# electric-imp-shield-v11.net
KiCad netlist of a schematic drawn in EAGLE
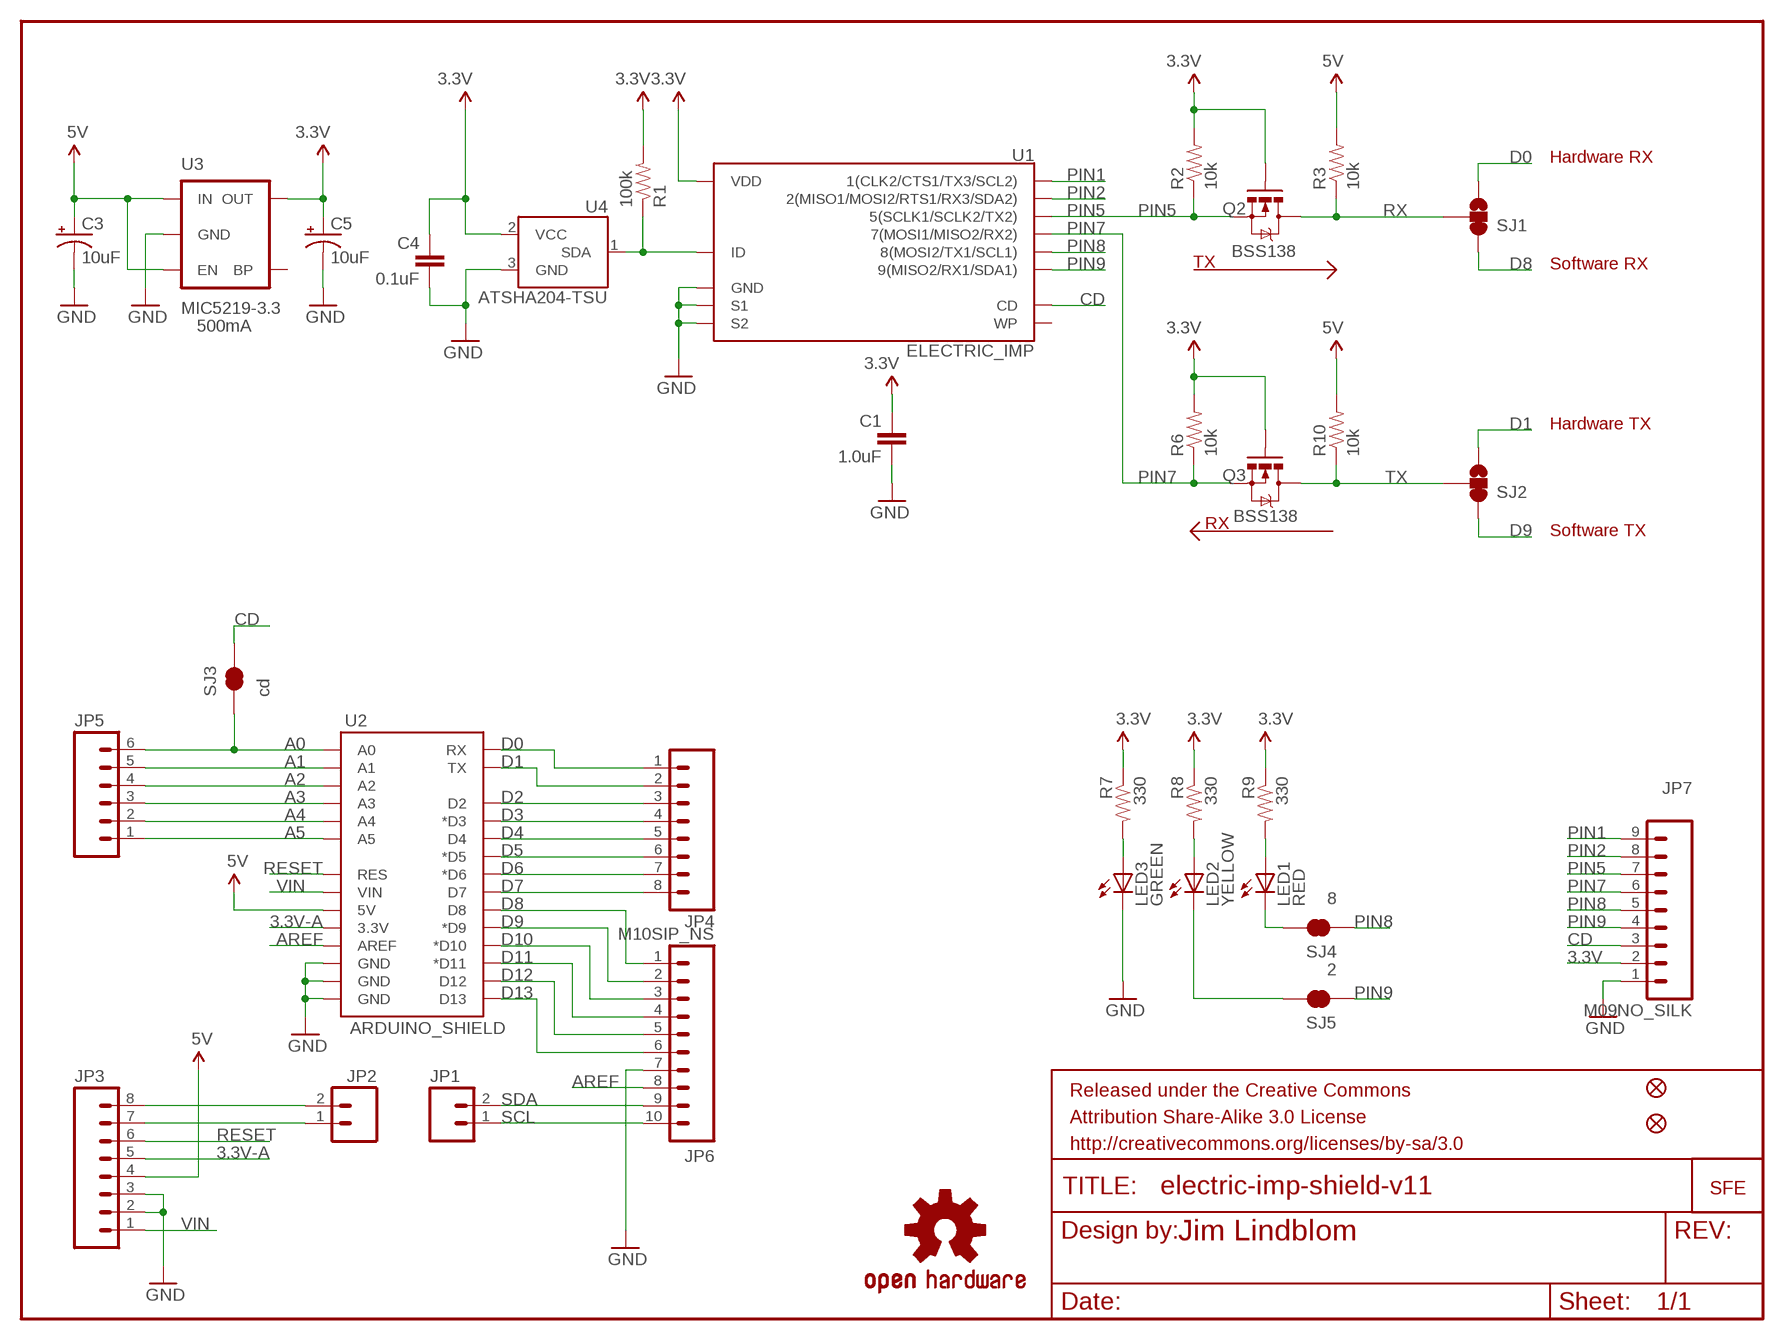
[diagram p0: schematic, sheet 1]

(export (version "E")
  (design (tool "Eeschema 10.0.6"))
  (components
    (comp (ref "C1")
      (value "1.0uF")
      (footprint "eagle-import:0402-CAP")
      (libsource (lib "eagle-import") (part "CAP0402-CAP"))
    )
    (comp (ref "C3")
      (value "10uF")
      (footprint "eagle-import:EIA3216")
      (libsource (lib "eagle-import") (part "CAP_POL1206"))
    )
    (comp (ref "C4")
      (value "0.1uF")
      (footprint "eagle-import:0402-CAP")
      (libsource (lib "eagle-import") (part "CAP0402-CAP"))
    )
    (comp (ref "C5")
      (value "10uF")
      (footprint "eagle-import:EIA3216")
      (libsource (lib "eagle-import") (part "CAP_POL1206"))
    )
    (comp (ref "JP1")
      (value "M021X02_NO_SILK")
      (footprint "eagle-import:1X02_NO_SILK")
      (libsource (lib "eagle-import") (part "M021X02_NO_SILK"))
    )
    (comp (ref "JP2")
      (value "M021X02_NO_SILK")
      (footprint "eagle-import:1X02_NO_SILK")
      (libsource (lib "eagle-import") (part "M021X02_NO_SILK"))
    )
    (comp (ref "JP3")
      (value "M08SIP_NS")
      (footprint "eagle-import:1X08_NO_SILK")
      (libsource (lib "eagle-import") (part "M08SIP_NS"))
    )
    (comp (ref "JP4")
      (value "M08SIP_NS")
      (footprint "eagle-import:1X08_NO_SILK")
      (libsource (lib "eagle-import") (part "M08SIP_NS"))
    )
    (comp (ref "JP5")
      (value "M06SIP_NS")
      (footprint "eagle-import:1X06_NO_SILK")
      (libsource (lib "eagle-import") (part "M06SIP_NS"))
    )
    (comp (ref "JP6")
      (value "M10SIP_NS")
      (footprint "eagle-import:1X10_NO_SILK")
      (libsource (lib "eagle-import") (part "M10SIP_NS"))
    )
    (comp (ref "JP7")
      (value "M09NO_SILK")
      (footprint "eagle-import:1X09_NO_SILK")
      (libsource (lib "eagle-import") (part "M09NO_SILK"))
    )
    (comp (ref "JP8")
      (value "FIDUCIALUFIDUCIAL")
      (footprint "eagle-import:MICRO-FIDUCIAL")
      (libsource (lib "eagle-import") (part "FIDUCIALUFIDUCIAL"))
    )
    (comp (ref "JP9")
      (value "FIDUCIALUFIDUCIAL")
      (footprint "eagle-import:MICRO-FIDUCIAL")
      (libsource (lib "eagle-import") (part "FIDUCIALUFIDUCIAL"))
    )
    (comp (ref "JP10")
      (value "LOGO-SFENW2")
      (footprint "eagle-import:SFE-NEW-WEB")
      (libsource (lib "eagle-import") (part "LOGO-SFENW2"))
    )
    (comp (ref "LED1")
      (value "RED")
      (footprint "eagle-import:LED-0603")
      (libsource (lib "eagle-import") (part "LED0603"))
    )
    (comp (ref "LED2")
      (value "YELLOW")
      (footprint "eagle-import:LED-0603")
      (libsource (lib "eagle-import") (part "LED0603"))
    )
    (comp (ref "LED3")
      (value "GREEN")
      (footprint "eagle-import:LED-0603")
      (libsource (lib "eagle-import") (part "LED0603"))
    )
    (comp (ref "Q2")
      (value "BSS138")
      (footprint "eagle-import:SOT23-3")
      (libsource (lib "eagle-import") (part "MOSFET-NCHANNELSMD"))
    )
    (comp (ref "Q3")
      (value "BSS138")
      (footprint "eagle-import:SOT23-3")
      (libsource (lib "eagle-import") (part "MOSFET-NCHANNELSMD"))
    )
    (comp (ref "R1")
      (value "100k")
      (footprint "eagle-import:0402-RES")
      (libsource (lib "eagle-import") (part "RESISTOR0402-RES"))
    )
    (comp (ref "R2")
      (value "10k")
      (footprint "eagle-import:0402-RES")
      (libsource (lib "eagle-import") (part "RESISTOR0402-RES"))
    )
    (comp (ref "R3")
      (value "10k")
      (footprint "eagle-import:0402-RES")
      (libsource (lib "eagle-import") (part "RESISTOR0402-RES"))
    )
    (comp (ref "R6")
      (value "10k")
      (footprint "eagle-import:0402-RES")
      (libsource (lib "eagle-import") (part "RESISTOR0402-RES"))
    )
    (comp (ref "R7")
      (value "330")
      (footprint "eagle-import:0402-RES")
      (libsource (lib "eagle-import") (part "RESISTOR0402-RES"))
    )
    (comp (ref "R8")
      (value "330")
      (footprint "eagle-import:0402-RES")
      (libsource (lib "eagle-import") (part "RESISTOR0402-RES"))
    )
    (comp (ref "R9")
      (value "330")
      (footprint "eagle-import:0402-RES")
      (libsource (lib "eagle-import") (part "RESISTOR0402-RES"))
    )
    (comp (ref "R10")
      (value "10k")
      (footprint "eagle-import:0402-RES")
      (libsource (lib "eagle-import") (part "RESISTOR0402-RES"))
    )
    (comp (ref "SJ1")
      (value "SOLDERJUMPER_2WAYS")
      (footprint "eagle-import:SJ_3")
      (libsource (lib "eagle-import") (part "SOLDERJUMPER_2WAYS"))
    )
    (comp (ref "SJ2")
      (value "SOLDERJUMPER_2WAYS")
      (footprint "eagle-import:SJ_3")
      (libsource (lib "eagle-import") (part "SOLDERJUMPER_2WAYS"))
    )
    (comp (ref "SJ3")
      (value "cd")
      (footprint "eagle-import:SJ_2S-TRACE")
      (libsource (lib "eagle-import") (part "SOLDERJUMPERTRACE"))
    )
    (comp (ref "SJ4")
      (value "8")
      (footprint "eagle-import:SJ_2S-TRACE")
      (libsource (lib "eagle-import") (part "SOLDERJUMPERTRACE"))
    )
    (comp (ref "SJ5")
      (value "2")
      (footprint "eagle-import:SJ_2S-TRACE")
      (libsource (lib "eagle-import") (part "SOLDERJUMPERTRACE"))
    )
    (comp (ref "U$7")
      (value "OSHW-LOGOS")
      (footprint "eagle-import:OSHW-LOGO-S")
      (libsource (lib "eagle-import") (part "OSHW-LOGOS"))
    )
    (comp (ref "U1")
      (value "ELECTRIC_IMP")
      (footprint "eagle-import:SD_MMC_SOCKET")
      (libsource (lib "eagle-import") (part "ELECTRIC_IMP"))
    )
    (comp (ref "U2")
      (value "ARDUINO_SHIELD")
      (footprint "eagle-import:DUEMILANOVE_SHIELD_NOHOLES_NOLABELS")
      (libsource (lib "eagle-import") (part "ARDUINO_SHIELDNOHOLESORLABELS"))
    )
    (comp (ref "U3")
      (value "MIC5219-3.3")
      (footprint "eagle-import:SOT23-5")
      (libsource (lib "eagle-import") (part "V_REG_LDOSMD"))
    )
    (comp (ref "U4")
      (value "ATSHA204-TSU")
      (footprint "eagle-import:SOT23-3")
      (libsource (lib "eagle-import") (part "ATSHA204-TSU"))
    )
  )
  (nets
    (net (code "1") (name "/3.3V-A") (class "Default")
      (node (ref "JP3") (pin "5") (pinfunction "5_5") (pintype "passive"))
      (node (ref "U2") (pin "3.3V") (pinfunction "3.3V_3.3V") (pintype "bidirectional"))
    )
    (net (code "2") (name "/A0") (class "Default")
      (node (ref "JP5") (pin "6") (pinfunction "6_6") (pintype "passive"))
      (node (ref "SJ3") (pin "1") (pinfunction "1_1") (pintype "passive"))
      (node (ref "U2") (pin "A0") (pinfunction "A0_A0") (pintype "bidirectional"))
    )
    (net (code "3") (name "/A1") (class "Default")
      (node (ref "JP5") (pin "5") (pinfunction "5_5") (pintype "passive"))
      (node (ref "U2") (pin "A1") (pinfunction "A1_A1") (pintype "bidirectional"))
    )
    (net (code "4") (name "/A2") (class "Default")
      (node (ref "JP5") (pin "4") (pinfunction "4_4") (pintype "passive"))
      (node (ref "U2") (pin "A2") (pinfunction "A2_A2") (pintype "bidirectional"))
    )
    (net (code "5") (name "/A3") (class "Default")
      (node (ref "JP5") (pin "3") (pinfunction "3_3") (pintype "passive"))
      (node (ref "U2") (pin "A3") (pinfunction "A3_A3") (pintype "bidirectional"))
    )
    (net (code "6") (name "/A4") (class "Default")
      (node (ref "JP5") (pin "2") (pinfunction "2_2") (pintype "passive"))
      (node (ref "U2") (pin "A4") (pinfunction "A4_A4") (pintype "bidirectional"))
    )
    (net (code "7") (name "/A5") (class "Default")
      (node (ref "JP5") (pin "1") (pinfunction "1_1") (pintype "passive"))
      (node (ref "U2") (pin "A5") (pinfunction "A5_A5") (pintype "bidirectional"))
    )
    (net (code "8") (name "/AREF") (class "Default")
      (node (ref "JP6") (pin "8") (pinfunction "8_8") (pintype "passive"))
      (node (ref "U2") (pin "AREF") (pinfunction "AREF_AREF") (pintype "bidirectional"))
    )
    (net (code "9") (name "/CD") (class "Default")
      (node (ref "JP7") (pin "3") (pinfunction "3_3") (pintype "passive"))
      (node (ref "SJ3") (pin "2") (pinfunction "2_2") (pintype "passive"))
      (node (ref "U1") (pin "CD") (pinfunction "CD_CD") (pintype "bidirectional"))
    )
    (net (code "10") (name "/D0") (class "Default")
      (node (ref "JP4") (pin "1") (pinfunction "1_1") (pintype "passive"))
      (node (ref "SJ1") (pin "3") (pinfunction "3_3") (pintype "passive"))
      (node (ref "U2") (pin "RX") (pinfunction "RX_RX") (pintype "bidirectional"))
    )
    (net (code "11") (name "/D1") (class "Default")
      (node (ref "JP4") (pin "2") (pinfunction "2_2") (pintype "passive"))
      (node (ref "SJ2") (pin "3") (pinfunction "3_3") (pintype "passive"))
      (node (ref "U2") (pin "TX") (pinfunction "TX_TX") (pintype "bidirectional"))
    )
    (net (code "12") (name "/D2") (class "Default")
      (node (ref "JP4") (pin "3") (pinfunction "3_3") (pintype "passive"))
      (node (ref "U2") (pin "D2") (pinfunction "D2_D2") (pintype "bidirectional"))
    )
    (net (code "13") (name "/D3") (class "Default")
      (node (ref "JP4") (pin "4") (pinfunction "4_4") (pintype "passive"))
      (node (ref "U2") (pin "D3") (pinfunction "*D3_D3") (pintype "bidirectional"))
    )
    (net (code "14") (name "/D4") (class "Default")
      (node (ref "JP4") (pin "5") (pinfunction "5_5") (pintype "passive"))
      (node (ref "U2") (pin "D4") (pinfunction "D4_D4") (pintype "bidirectional"))
    )
    (net (code "15") (name "/D5") (class "Default")
      (node (ref "JP4") (pin "6") (pinfunction "6_6") (pintype "passive"))
      (node (ref "U2") (pin "D5") (pinfunction "*D5_D5") (pintype "bidirectional"))
    )
    (net (code "16") (name "/D6") (class "Default")
      (node (ref "JP4") (pin "7") (pinfunction "7_7") (pintype "passive"))
      (node (ref "U2") (pin "D6") (pinfunction "*D6_D6") (pintype "bidirectional"))
    )
    (net (code "17") (name "/D7") (class "Default")
      (node (ref "JP4") (pin "8") (pinfunction "8_8") (pintype "passive"))
      (node (ref "U2") (pin "D7") (pinfunction "D7_D7") (pintype "bidirectional"))
    )
    (net (code "18") (name "/D8") (class "Default")
      (node (ref "JP6") (pin "1") (pinfunction "1_1") (pintype "passive"))
      (node (ref "SJ1") (pin "1") (pinfunction "1_1") (pintype "passive"))
      (node (ref "U2") (pin "D8") (pinfunction "D8_D8") (pintype "bidirectional"))
    )
    (net (code "19") (name "/D9") (class "Default")
      (node (ref "JP6") (pin "2") (pinfunction "2_2") (pintype "passive"))
      (node (ref "SJ2") (pin "1") (pinfunction "1_1") (pintype "passive"))
      (node (ref "U2") (pin "D9") (pinfunction "*D9_D9") (pintype "bidirectional"))
    )
    (net (code "20") (name "/D10") (class "Default")
      (node (ref "JP6") (pin "3") (pinfunction "3_3") (pintype "passive"))
      (node (ref "U2") (pin "D10") (pinfunction "*D10_D10") (pintype "bidirectional"))
    )
    (net (code "21") (name "/D11") (class "Default")
      (node (ref "JP6") (pin "4") (pinfunction "4_4") (pintype "passive"))
      (node (ref "U2") (pin "D11") (pinfunction "*D11_D11") (pintype "bidirectional"))
    )
    (net (code "22") (name "/D12") (class "Default")
      (node (ref "JP6") (pin "5") (pinfunction "5_5") (pintype "passive"))
      (node (ref "U2") (pin "D12") (pinfunction "D12_D12") (pintype "bidirectional"))
    )
    (net (code "23") (name "/D13") (class "Default")
      (node (ref "JP6") (pin "6") (pinfunction "6_6") (pintype "passive"))
      (node (ref "U2") (pin "D13") (pinfunction "D13_D13") (pintype "bidirectional"))
    )
    (net (code "24") (name "/PIN1") (class "Default")
      (node (ref "JP7") (pin "9") (pinfunction "9_9") (pintype "passive"))
      (node (ref "U1") (pin "1") (pinfunction "1(CLK2/CTS1/TX3/SCL2)_1") (pintype "bidirectional"))
    )
    (net (code "25") (name "/PIN2") (class "Default")
      (node (ref "JP7") (pin "8") (pinfunction "8_8") (pintype "passive"))
      (node (ref "U1") (pin "2") (pinfunction "2(MISO1/MOSI2/RTS1/RX3/SDA2)_2") (pintype "bidirectional"))
    )
    (net (code "26") (name "/PIN5") (class "Default")
      (node (ref "JP7") (pin "7") (pinfunction "7_7") (pintype "passive"))
      (node (ref "Q2") (pin "2") (pinfunction "S_2") (pintype "passive"))
      (node (ref "R2") (pin "1") (pinfunction "1_1") (pintype "passive"))
      (node (ref "U1") (pin "5") (pinfunction "5(SCLK1/SCLK2/TX2)_5") (pintype "bidirectional"))
    )
    (net (code "27") (name "/PIN7") (class "Default")
      (node (ref "JP7") (pin "6") (pinfunction "6_6") (pintype "passive"))
      (node (ref "Q3") (pin "2") (pinfunction "S_2") (pintype "passive"))
      (node (ref "R6") (pin "1") (pinfunction "1_1") (pintype "passive"))
      (node (ref "U1") (pin "7") (pinfunction "7(MOSI1/MISO2/RX2)_7") (pintype "bidirectional"))
    )
    (net (code "28") (name "/PIN8") (class "Default")
      (node (ref "JP7") (pin "5") (pinfunction "5_5") (pintype "passive"))
      (node (ref "SJ4") (pin "1") (pinfunction "1_1") (pintype "passive"))
      (node (ref "U1") (pin "8") (pinfunction "8(MOSI2/TX1/SCL1)_8") (pintype "bidirectional"))
    )
    (net (code "29") (name "/PIN9") (class "Default")
      (node (ref "JP7") (pin "4") (pinfunction "4_4") (pintype "passive"))
      (node (ref "SJ5") (pin "1") (pinfunction "1_1") (pintype "passive"))
      (node (ref "U1") (pin "9") (pinfunction "9(MISO2/RX1/SDA1)_9") (pintype "bidirectional"))
    )
    (net (code "30") (name "/RESET") (class "Default")
      (node (ref "JP3") (pin "6") (pinfunction "6_6") (pintype "passive"))
      (node (ref "U2") (pin "RES") (pinfunction "RES_RES") (pintype "bidirectional"))
    )
    (net (code "31") (name "/RX") (class "Default")
      (node (ref "Q2") (pin "3") (pinfunction "D_3") (pintype "passive"))
      (node (ref "R3") (pin "1") (pinfunction "1_1") (pintype "passive"))
      (node (ref "SJ1") (pin "2") (pinfunction "2_2") (pintype "passive"))
    )
    (net (code "32") (name "/SCL") (class "Default")
      (node (ref "JP1") (pin "1") (pinfunction "1_1") (pintype "passive"))
      (node (ref "JP6") (pin "10") (pinfunction "10_10") (pintype "passive"))
    )
    (net (code "33") (name "/SDA") (class "Default")
      (node (ref "JP1") (pin "2") (pinfunction "2_2") (pintype "passive"))
      (node (ref "JP6") (pin "9") (pinfunction "9_9") (pintype "passive"))
    )
    (net (code "34") (name "/TX") (class "Default")
      (node (ref "Q3") (pin "3") (pinfunction "D_3") (pintype "passive"))
      (node (ref "R10") (pin "1") (pinfunction "1_1") (pintype "passive"))
      (node (ref "SJ2") (pin "2") (pinfunction "2_2") (pintype "passive"))
    )
    (net (code "35") (name "/VIN") (class "Default")
      (node (ref "JP3") (pin "1") (pinfunction "1_1") (pintype "passive"))
      (node (ref "U2") (pin "VIN") (pinfunction "VIN_VIN") (pintype "bidirectional"))
    )
    (net (code "36") (name "3.3V") (class "Default")
      (node (ref "C1") (pin "1") (pinfunction "1_1") (pintype "passive"))
      (node (ref "C4") (pin "1") (pinfunction "1_1") (pintype "passive"))
      (node (ref "C5") (pin "A") (pinfunction "+_A") (pintype "passive"))
      (node (ref "JP7") (pin "2") (pinfunction "2_2") (pintype "passive"))
      (node (ref "Q2") (pin "1") (pinfunction "G_1") (pintype "passive"))
      (node (ref "Q3") (pin "1") (pinfunction "G_1") (pintype "passive"))
      (node (ref "R1") (pin "2") (pinfunction "2_2") (pintype "passive"))
      (node (ref "R2") (pin "2") (pinfunction "2_2") (pintype "passive"))
      (node (ref "R6") (pin "2") (pinfunction "2_2") (pintype "passive"))
      (node (ref "R7") (pin "1") (pinfunction "1_1") (pintype "passive"))
      (node (ref "R8") (pin "1") (pinfunction "1_1") (pintype "passive"))
      (node (ref "R9") (pin "1") (pinfunction "1_1") (pintype "passive"))
      (node (ref "U1") (pin "4") (pinfunction "VDD_4") (pintype "bidirectional"))
      (node (ref "U3") (pin "5") (pinfunction "OUT_5") (pintype "passive"))
      (node (ref "U4") (pin "2") (pinfunction "VCC_2") (pintype "bidirectional"))
    )
    (net (code "37") (name "5V") (class "Default")
      (node (ref "C3") (pin "A") (pinfunction "+_A") (pintype "passive"))
      (node (ref "JP3") (pin "4") (pinfunction "4_4") (pintype "passive"))
      (node (ref "R10") (pin "2") (pinfunction "2_2") (pintype "passive"))
      (node (ref "R3") (pin "2") (pinfunction "2_2") (pintype "passive"))
      (node (ref "U2") (pin "5V") (pinfunction "5V_5V") (pintype "bidirectional"))
      (node (ref "U3") (pin "1") (pinfunction "IN_1") (pintype "input"))
      (node (ref "U3") (pin "3") (pinfunction "EN_3") (pintype "input"))
    )
    (net (code "38") (name "GND") (class "Default")
      (node (ref "C1") (pin "2") (pinfunction "2_2") (pintype "passive"))
      (node (ref "C3") (pin "C") (pinfunction "-_C") (pintype "passive"))
      (node (ref "C4") (pin "2") (pinfunction "2_2") (pintype "passive"))
      (node (ref "C5") (pin "C") (pinfunction "-_C") (pintype "passive"))
      (node (ref "JP3") (pin "2") (pinfunction "2_2") (pintype "passive"))
      (node (ref "JP3") (pin "3") (pinfunction "3_3") (pintype "passive"))
      (node (ref "JP6") (pin "7") (pinfunction "7_7") (pintype "passive"))
      (node (ref "JP7") (pin "1") (pinfunction "1_1") (pintype "passive"))
      (node (ref "LED3") (pin "C") (pinfunction "C_C") (pintype "passive"))
      (node (ref "U1") (pin "3") (pinfunction "GND_3") (pintype "bidirectional"))
      (node (ref "U1") (pin "S1") (pinfunction "S1_S1") (pintype "bidirectional"))
      (node (ref "U1") (pin "S2") (pinfunction "S2_S2") (pintype "bidirectional"))
      (node (ref "U2") (pin "GND@0") (pinfunction "GND_GND@0") (pintype "bidirectional"))
      (node (ref "U2") (pin "GND@1") (pinfunction "GND_GND@1") (pintype "bidirectional"))
      (node (ref "U2") (pin "GND@2") (pinfunction "GND_GND@2") (pintype "bidirectional"))
      (node (ref "U3") (pin "2") (pinfunction "GND_2") (pintype "input"))
      (node (ref "U4") (pin "3") (pinfunction "GND_3") (pintype "bidirectional"))
    )
    (net (code "39") (name "Net-(JP2-Pad1)") (class "Default")
      (node (ref "JP2") (pin "1") (pinfunction "1_1") (pintype "passive"))
      (node (ref "JP3") (pin "7") (pinfunction "7_7") (pintype "passive"))
    )
    (net (code "40") (name "Net-(JP2-Pad2)") (class "Default")
      (node (ref "JP2") (pin "2") (pinfunction "2_2") (pintype "passive"))
      (node (ref "JP3") (pin "8") (pinfunction "8_8") (pintype "passive"))
    )
    (net (code "41") (name "Net-(LED1-PadA)") (class "Default")
      (node (ref "LED1") (pin "A") (pinfunction "A_A") (pintype "passive"))
      (node (ref "R9") (pin "2") (pinfunction "2_2") (pintype "passive"))
    )
    (net (code "42") (name "Net-(LED1-PadC)") (class "Default")
      (node (ref "LED1") (pin "C") (pinfunction "C_C") (pintype "passive"))
      (node (ref "SJ4") (pin "2") (pinfunction "2_2") (pintype "passive"))
    )
    (net (code "43") (name "Net-(LED2-PadA)") (class "Default")
      (node (ref "LED2") (pin "A") (pinfunction "A_A") (pintype "passive"))
      (node (ref "R8") (pin "2") (pinfunction "2_2") (pintype "passive"))
    )
    (net (code "44") (name "Net-(LED2-PadC)") (class "Default")
      (node (ref "LED2") (pin "C") (pinfunction "C_C") (pintype "passive"))
      (node (ref "SJ5") (pin "2") (pinfunction "2_2") (pintype "passive"))
    )
    (net (code "45") (name "Net-(LED3-PadA)") (class "Default")
      (node (ref "LED3") (pin "A") (pinfunction "A_A") (pintype "passive"))
      (node (ref "R7") (pin "2") (pinfunction "2_2") (pintype "passive"))
    )
    (net (code "46") (name "Net-(U1-ID)") (class "Default")
      (node (ref "R1") (pin "1") (pinfunction "1_1") (pintype "passive"))
      (node (ref "U1") (pin "6") (pinfunction "ID_6") (pintype "bidirectional"))
      (node (ref "U4") (pin "1") (pinfunction "SDA_1") (pintype "bidirectional"))
    )
    (net (code "47") (name "unconnected-(U1-PadWP)") (class "Default")
      (node (ref "U1") (pin "WP") (pinfunction "WP_WP") (pintype "bidirectional"))
    )
    (net (code "48") (name "unconnected-(U3-BP-Pad4)") (class "Default")
      (node (ref "U3") (pin "4") (pinfunction "BP_4") (pintype "input"))
    )
  )
)
